# LEDKEY.net
KiCad netlist of a schematic drawn in Altium Designer
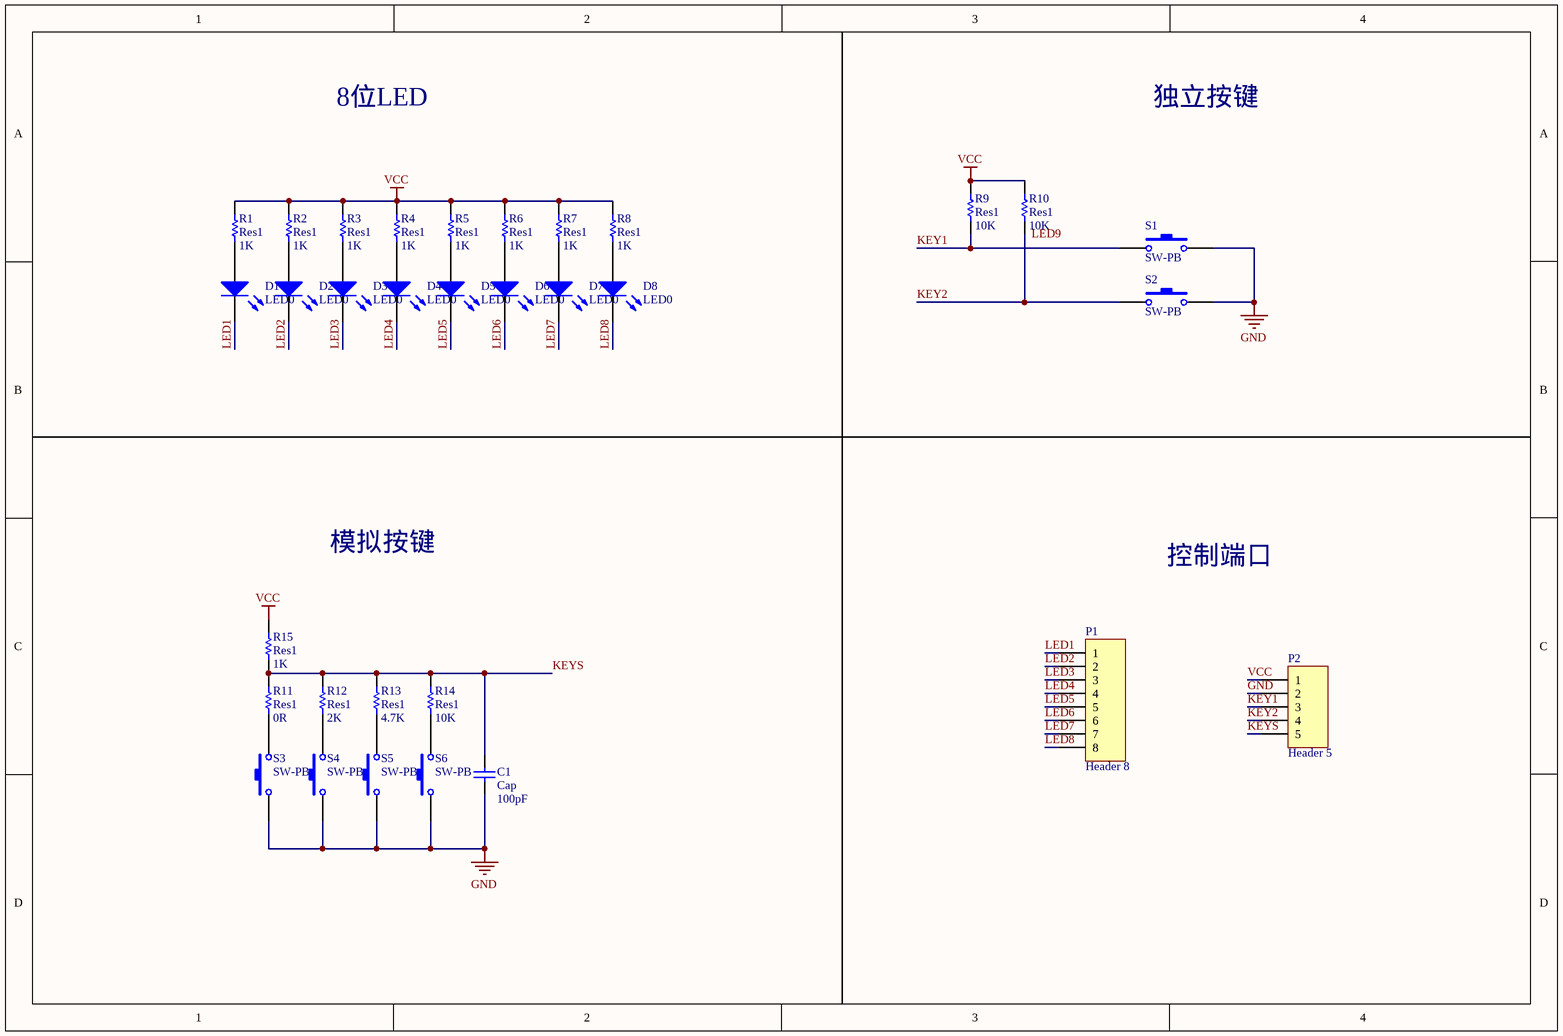
[diagram p0: LEDKEY.SchDoc]

(export (version "E")
  (design (tool "Eeschema 10.0.6"))
  (components
    (comp (ref "C1")
      (value "Cap")
      (footprint "C0603")
      (description "Capacitor")
      (fields (field (name "ALTIUM_VALUE") "100pF") (field (name "PUBLISHER") "Altium Limited"))
      (libsource (lib "LEDKEY") (part "Cap"))
    )
    (comp (ref "D1")
      (value "LED0")
      (footprint "LED0603")
      (description "Typical INFRARED GaAs LED")
      (fields (field (name "PUBLISHER") "Altium Limited"))
      (libsource (lib "LEDKEY") (part "LED"))
    )
    (comp (ref "D2")
      (value "LED0")
      (footprint "LED0603")
      (description "Typical INFRARED GaAs LED")
      (fields (field (name "PUBLISHER") "Altium Limited"))
      (libsource (lib "LEDKEY") (part "LED"))
    )
    (comp (ref "D3")
      (value "LED0")
      (footprint "LED0603")
      (description "Typical INFRARED GaAs LED")
      (fields (field (name "PUBLISHER") "Altium Limited"))
      (libsource (lib "LEDKEY") (part "LED"))
    )
    (comp (ref "D4")
      (value "LED0")
      (footprint "LED0603")
      (description "Typical INFRARED GaAs LED")
      (fields (field (name "PUBLISHER") "Altium Limited"))
      (libsource (lib "LEDKEY") (part "LED"))
    )
    (comp (ref "D5")
      (value "LED0")
      (footprint "LED0603")
      (description "Typical INFRARED GaAs LED")
      (fields (field (name "PUBLISHER") "Altium Limited"))
      (libsource (lib "LEDKEY") (part "LED"))
    )
    (comp (ref "D6")
      (value "LED0")
      (footprint "LED0603")
      (description "Typical INFRARED GaAs LED")
      (fields (field (name "PUBLISHER") "Altium Limited"))
      (libsource (lib "LEDKEY") (part "LED"))
    )
    (comp (ref "D7")
      (value "LED0")
      (footprint "LED0603")
      (description "Typical INFRARED GaAs LED")
      (fields (field (name "PUBLISHER") "Altium Limited"))
      (libsource (lib "LEDKEY") (part "LED"))
    )
    (comp (ref "D8")
      (value "LED0")
      (footprint "LED0603")
      (description "Typical INFRARED GaAs LED")
      (fields (field (name "PUBLISHER") "Altium Limited"))
      (libsource (lib "LEDKEY") (part "LED"))
    )
    (comp (ref "P1")
      (value "Header 8")
      (footprint "HDR1X8")
      (description "Header, 8-Pin")
      (fields (field (name "PUBLISHER") "Altium Limited"))
      (libsource (lib "LEDKEY") (part "Header 8"))
    )
    (comp (ref "P2")
      (value "Header 5")
      (footprint "HDR1X5")
      (description "Header, 5-Pin")
      (fields (field (name "PUBLISHER") "Altium Limited"))
      (libsource (lib "LEDKEY") (part "Header 5"))
    )
    (comp (ref "R1")
      (value "Res1")
      (footprint "R0603")
      (description "Resistor")
      (fields (field (name "ALTIUM_VALUE") "1K") (field (name "PUBLISHER") "Altium Limited"))
      (libsource (lib "LEDKEY") (part "Res"))
    )
    (comp (ref "R2")
      (value "Res1")
      (footprint "R0603")
      (description "Resistor")
      (fields (field (name "ALTIUM_VALUE") "1K") (field (name "PUBLISHER") "Altium Limited"))
      (libsource (lib "LEDKEY") (part "Res"))
    )
    (comp (ref "R3")
      (value "Res1")
      (footprint "R0603")
      (description "Resistor")
      (fields (field (name "ALTIUM_VALUE") "1K") (field (name "PUBLISHER") "Altium Limited"))
      (libsource (lib "LEDKEY") (part "Res"))
    )
    (comp (ref "R4")
      (value "Res1")
      (footprint "R0603")
      (description "Resistor")
      (fields (field (name "ALTIUM_VALUE") "1K") (field (name "PUBLISHER") "Altium Limited"))
      (libsource (lib "LEDKEY") (part "Res"))
    )
    (comp (ref "R5")
      (value "Res1")
      (footprint "R0603")
      (description "Resistor")
      (fields (field (name "ALTIUM_VALUE") "1K") (field (name "PUBLISHER") "Altium Limited"))
      (libsource (lib "LEDKEY") (part "Res"))
    )
    (comp (ref "R6")
      (value "Res1")
      (footprint "R0603")
      (description "Resistor")
      (fields (field (name "ALTIUM_VALUE") "1K") (field (name "PUBLISHER") "Altium Limited"))
      (libsource (lib "LEDKEY") (part "Res"))
    )
    (comp (ref "R7")
      (value "Res1")
      (footprint "R0603")
      (description "Resistor")
      (fields (field (name "ALTIUM_VALUE") "1K") (field (name "PUBLISHER") "Altium Limited"))
      (libsource (lib "LEDKEY") (part "Res"))
    )
    (comp (ref "R8")
      (value "Res1")
      (footprint "R0603")
      (description "Resistor")
      (fields (field (name "ALTIUM_VALUE") "1K") (field (name "PUBLISHER") "Altium Limited"))
      (libsource (lib "LEDKEY") (part "Res"))
    )
    (comp (ref "R9")
      (value "Res1")
      (footprint "R0603")
      (description "Resistor")
      (fields (field (name "ALTIUM_VALUE") "10K") (field (name "PUBLISHER") "Altium Limited"))
      (libsource (lib "LEDKEY") (part "Res"))
    )
    (comp (ref "R10")
      (value "Res1")
      (footprint "R0603")
      (description "Resistor")
      (fields (field (name "ALTIUM_VALUE") "10K") (field (name "PUBLISHER") "Altium Limited"))
      (libsource (lib "LEDKEY") (part "Res"))
    )
    (comp (ref "R11")
      (value "Res1")
      (footprint "R0603")
      (description "Resistor")
      (fields (field (name "ALTIUM_VALUE") "0R") (field (name "PUBLISHER") "Altium Limited"))
      (libsource (lib "LEDKEY") (part "Res"))
    )
    (comp (ref "R12")
      (value "Res1")
      (footprint "R0603")
      (description "Resistor")
      (fields (field (name "ALTIUM_VALUE") "2K") (field (name "PUBLISHER") "Altium Limited"))
      (libsource (lib "LEDKEY") (part "Res"))
    )
    (comp (ref "R13")
      (value "Res1")
      (footprint "R0603")
      (description "Resistor")
      (fields (field (name "ALTIUM_VALUE") "4.7K") (field (name "PUBLISHER") "Altium Limited"))
      (libsource (lib "LEDKEY") (part "Res"))
    )
    (comp (ref "R14")
      (value "Res1")
      (footprint "R0603")
      (description "Resistor")
      (fields (field (name "ALTIUM_VALUE") "10K") (field (name "PUBLISHER") "Altium Limited"))
      (libsource (lib "LEDKEY") (part "Res"))
    )
    (comp (ref "R15")
      (value "Res1")
      (footprint "R0603")
      (description "Resistor")
      (fields (field (name "ALTIUM_VALUE") "1K") (field (name "PUBLISHER") "Altium Limited"))
      (libsource (lib "LEDKEY") (part "Res"))
    )
    (comp (ref "S1")
      (value "SW-PB")
      (footprint "SW-PB")
      (description "Switch")
      (fields (field (name "PUBLISHER") "Altium Limited"))
      (libsource (lib "LEDKEY") (part "SW-PB"))
    )
    (comp (ref "S2")
      (value "SW-PB")
      (footprint "SW-PB")
      (description "Switch")
      (fields (field (name "PUBLISHER") "Altium Limited"))
      (libsource (lib "LEDKEY") (part "SW-PB"))
    )
    (comp (ref "S3")
      (value "SW-PB")
      (footprint "SW-PB")
      (description "Switch")
      (fields (field (name "PUBLISHER") "Altium Limited"))
      (libsource (lib "LEDKEY") (part "SW-PB"))
    )
    (comp (ref "S4")
      (value "SW-PB")
      (footprint "SW-PB")
      (description "Switch")
      (fields (field (name "PUBLISHER") "Altium Limited"))
      (libsource (lib "LEDKEY") (part "SW-PB"))
    )
    (comp (ref "S5")
      (value "SW-PB")
      (footprint "SW-PB")
      (description "Switch")
      (fields (field (name "PUBLISHER") "Altium Limited"))
      (libsource (lib "LEDKEY") (part "SW-PB"))
    )
    (comp (ref "S6")
      (value "SW-PB")
      (footprint "SW-PB")
      (description "Switch")
      (fields (field (name "PUBLISHER") "Altium Limited"))
      (libsource (lib "LEDKEY") (part "SW-PB"))
    )
  )
  (nets
    (net (code "1") (name "/KEY1") (class "Default")
      (node (ref "P2") (pin "3") (pinfunction "3_3") (pintype "passive"))
      (node (ref "R9") (pin "1") (pinfunction "1_1") (pintype "passive"))
      (node (ref "S1") (pin "1") (pinfunction "1_1") (pintype "passive"))
    )
    (net (code "2") (name "/KEY2") (class "Default")
      (node (ref "P2") (pin "4") (pinfunction "4_4") (pintype "passive"))
      (node (ref "R10") (pin "1") (pinfunction "1_1") (pintype "passive"))
      (node (ref "S2") (pin "1") (pinfunction "1_1") (pintype "passive"))
    )
    (net (code "3") (name "/KEYS") (class "Default")
      (node (ref "C1") (pin "2") (pinfunction "2_2") (pintype "passive"))
      (node (ref "P2") (pin "5") (pinfunction "5_5") (pintype "passive"))
      (node (ref "R11") (pin "2") (pinfunction "2_2") (pintype "passive"))
      (node (ref "R12") (pin "2") (pinfunction "2_2") (pintype "passive"))
      (node (ref "R13") (pin "2") (pinfunction "2_2") (pintype "passive"))
      (node (ref "R14") (pin "2") (pinfunction "2_2") (pintype "passive"))
      (node (ref "R15") (pin "1") (pinfunction "1_1") (pintype "passive"))
    )
    (net (code "4") (name "/LED1") (class "Default")
      (node (ref "D1") (pin "1") (pinfunction "K_1") (pintype "passive"))
      (node (ref "P1") (pin "1") (pinfunction "1_1") (pintype "passive"))
    )
    (net (code "5") (name "/LED2") (class "Default")
      (node (ref "D2") (pin "1") (pinfunction "K_1") (pintype "passive"))
      (node (ref "P1") (pin "2") (pinfunction "2_2") (pintype "passive"))
    )
    (net (code "6") (name "/LED3") (class "Default")
      (node (ref "D3") (pin "1") (pinfunction "K_1") (pintype "passive"))
      (node (ref "P1") (pin "3") (pinfunction "3_3") (pintype "passive"))
    )
    (net (code "7") (name "/LED4") (class "Default")
      (node (ref "D4") (pin "1") (pinfunction "K_1") (pintype "passive"))
      (node (ref "P1") (pin "4") (pinfunction "4_4") (pintype "passive"))
    )
    (net (code "8") (name "/LED5") (class "Default")
      (node (ref "D5") (pin "1") (pinfunction "K_1") (pintype "passive"))
      (node (ref "P1") (pin "5") (pinfunction "5_5") (pintype "passive"))
    )
    (net (code "9") (name "/LED6") (class "Default")
      (node (ref "D6") (pin "1") (pinfunction "K_1") (pintype "passive"))
      (node (ref "P1") (pin "6") (pinfunction "6_6") (pintype "passive"))
    )
    (net (code "10") (name "/LED7") (class "Default")
      (node (ref "D7") (pin "1") (pinfunction "K_1") (pintype "passive"))
      (node (ref "P1") (pin "7") (pinfunction "7_7") (pintype "passive"))
    )
    (net (code "11") (name "/LED8") (class "Default")
      (node (ref "D8") (pin "1") (pinfunction "K_1") (pintype "passive"))
      (node (ref "P1") (pin "8") (pinfunction "8_8") (pintype "passive"))
    )
    (net (code "13") (name "GND") (class "Default")
      (node (ref "C1") (pin "1") (pinfunction "1_1") (pintype "passive"))
      (node (ref "P2") (pin "2") (pinfunction "2_2") (pintype "passive"))
      (node (ref "S1") (pin "2") (pinfunction "2_2") (pintype "passive"))
      (node (ref "S2") (pin "2") (pinfunction "2_2") (pintype "passive"))
      (node (ref "S3") (pin "1") (pinfunction "1_1") (pintype "passive"))
      (node (ref "S4") (pin "1") (pinfunction "1_1") (pintype "passive"))
      (node (ref "S5") (pin "1") (pinfunction "1_1") (pintype "passive"))
      (node (ref "S6") (pin "1") (pinfunction "1_1") (pintype "passive"))
    )
    (net (code "14") (name "Net-(D1-A)") (class "Default")
      (node (ref "D1") (pin "2") (pinfunction "A_2") (pintype "passive"))
      (node (ref "R1") (pin "1") (pinfunction "1_1") (pintype "passive"))
    )
    (net (code "15") (name "Net-(D2-A)") (class "Default")
      (node (ref "D2") (pin "2") (pinfunction "A_2") (pintype "passive"))
      (node (ref "R2") (pin "1") (pinfunction "1_1") (pintype "passive"))
    )
    (net (code "16") (name "Net-(D3-A)") (class "Default")
      (node (ref "D3") (pin "2") (pinfunction "A_2") (pintype "passive"))
      (node (ref "R3") (pin "1") (pinfunction "1_1") (pintype "passive"))
    )
    (net (code "17") (name "Net-(D4-A)") (class "Default")
      (node (ref "D4") (pin "2") (pinfunction "A_2") (pintype "passive"))
      (node (ref "R4") (pin "1") (pinfunction "1_1") (pintype "passive"))
    )
    (net (code "18") (name "Net-(D5-A)") (class "Default")
      (node (ref "D5") (pin "2") (pinfunction "A_2") (pintype "passive"))
      (node (ref "R5") (pin "1") (pinfunction "1_1") (pintype "passive"))
    )
    (net (code "19") (name "Net-(D6-A)") (class "Default")
      (node (ref "D6") (pin "2") (pinfunction "A_2") (pintype "passive"))
      (node (ref "R6") (pin "1") (pinfunction "1_1") (pintype "passive"))
    )
    (net (code "20") (name "Net-(D7-A)") (class "Default")
      (node (ref "D7") (pin "2") (pinfunction "A_2") (pintype "passive"))
      (node (ref "R7") (pin "1") (pinfunction "1_1") (pintype "passive"))
    )
    (net (code "21") (name "Net-(D8-A)") (class "Default")
      (node (ref "D8") (pin "2") (pinfunction "A_2") (pintype "passive"))
      (node (ref "R8") (pin "1") (pinfunction "1_1") (pintype "passive"))
    )
    (net (code "22") (name "Net-(R11-Pad1)") (class "Default")
      (node (ref "R11") (pin "1") (pinfunction "1_1") (pintype "passive"))
      (node (ref "S3") (pin "2") (pinfunction "2_2") (pintype "passive"))
    )
    (net (code "23") (name "Net-(R12-Pad1)") (class "Default")
      (node (ref "R12") (pin "1") (pinfunction "1_1") (pintype "passive"))
      (node (ref "S4") (pin "2") (pinfunction "2_2") (pintype "passive"))
    )
    (net (code "24") (name "Net-(R13-Pad1)") (class "Default")
      (node (ref "R13") (pin "1") (pinfunction "1_1") (pintype "passive"))
      (node (ref "S5") (pin "2") (pinfunction "2_2") (pintype "passive"))
    )
    (net (code "25") (name "Net-(R14-Pad1)") (class "Default")
      (node (ref "R14") (pin "1") (pinfunction "1_1") (pintype "passive"))
      (node (ref "S6") (pin "2") (pinfunction "2_2") (pintype "passive"))
    )
    (net (code "26") (name "VCC") (class "Default")
      (node (ref "P2") (pin "1") (pinfunction "1_1") (pintype "passive"))
      (node (ref "R1") (pin "2") (pinfunction "2_2") (pintype "passive"))
      (node (ref "R10") (pin "2") (pinfunction "2_2") (pintype "passive"))
      (node (ref "R15") (pin "2") (pinfunction "2_2") (pintype "passive"))
      (node (ref "R2") (pin "2") (pinfunction "2_2") (pintype "passive"))
      (node (ref "R3") (pin "2") (pinfunction "2_2") (pintype "passive"))
      (node (ref "R4") (pin "2") (pinfunction "2_2") (pintype "passive"))
      (node (ref "R5") (pin "2") (pinfunction "2_2") (pintype "passive"))
      (node (ref "R6") (pin "2") (pinfunction "2_2") (pintype "passive"))
      (node (ref "R7") (pin "2") (pinfunction "2_2") (pintype "passive"))
      (node (ref "R8") (pin "2") (pinfunction "2_2") (pintype "passive"))
      (node (ref "R9") (pin "2") (pinfunction "2_2") (pintype "passive"))
    )
  )
)
